# Thetis_RevF2_SCH.net
KiCad netlist of a schematic drawn in EAGLE
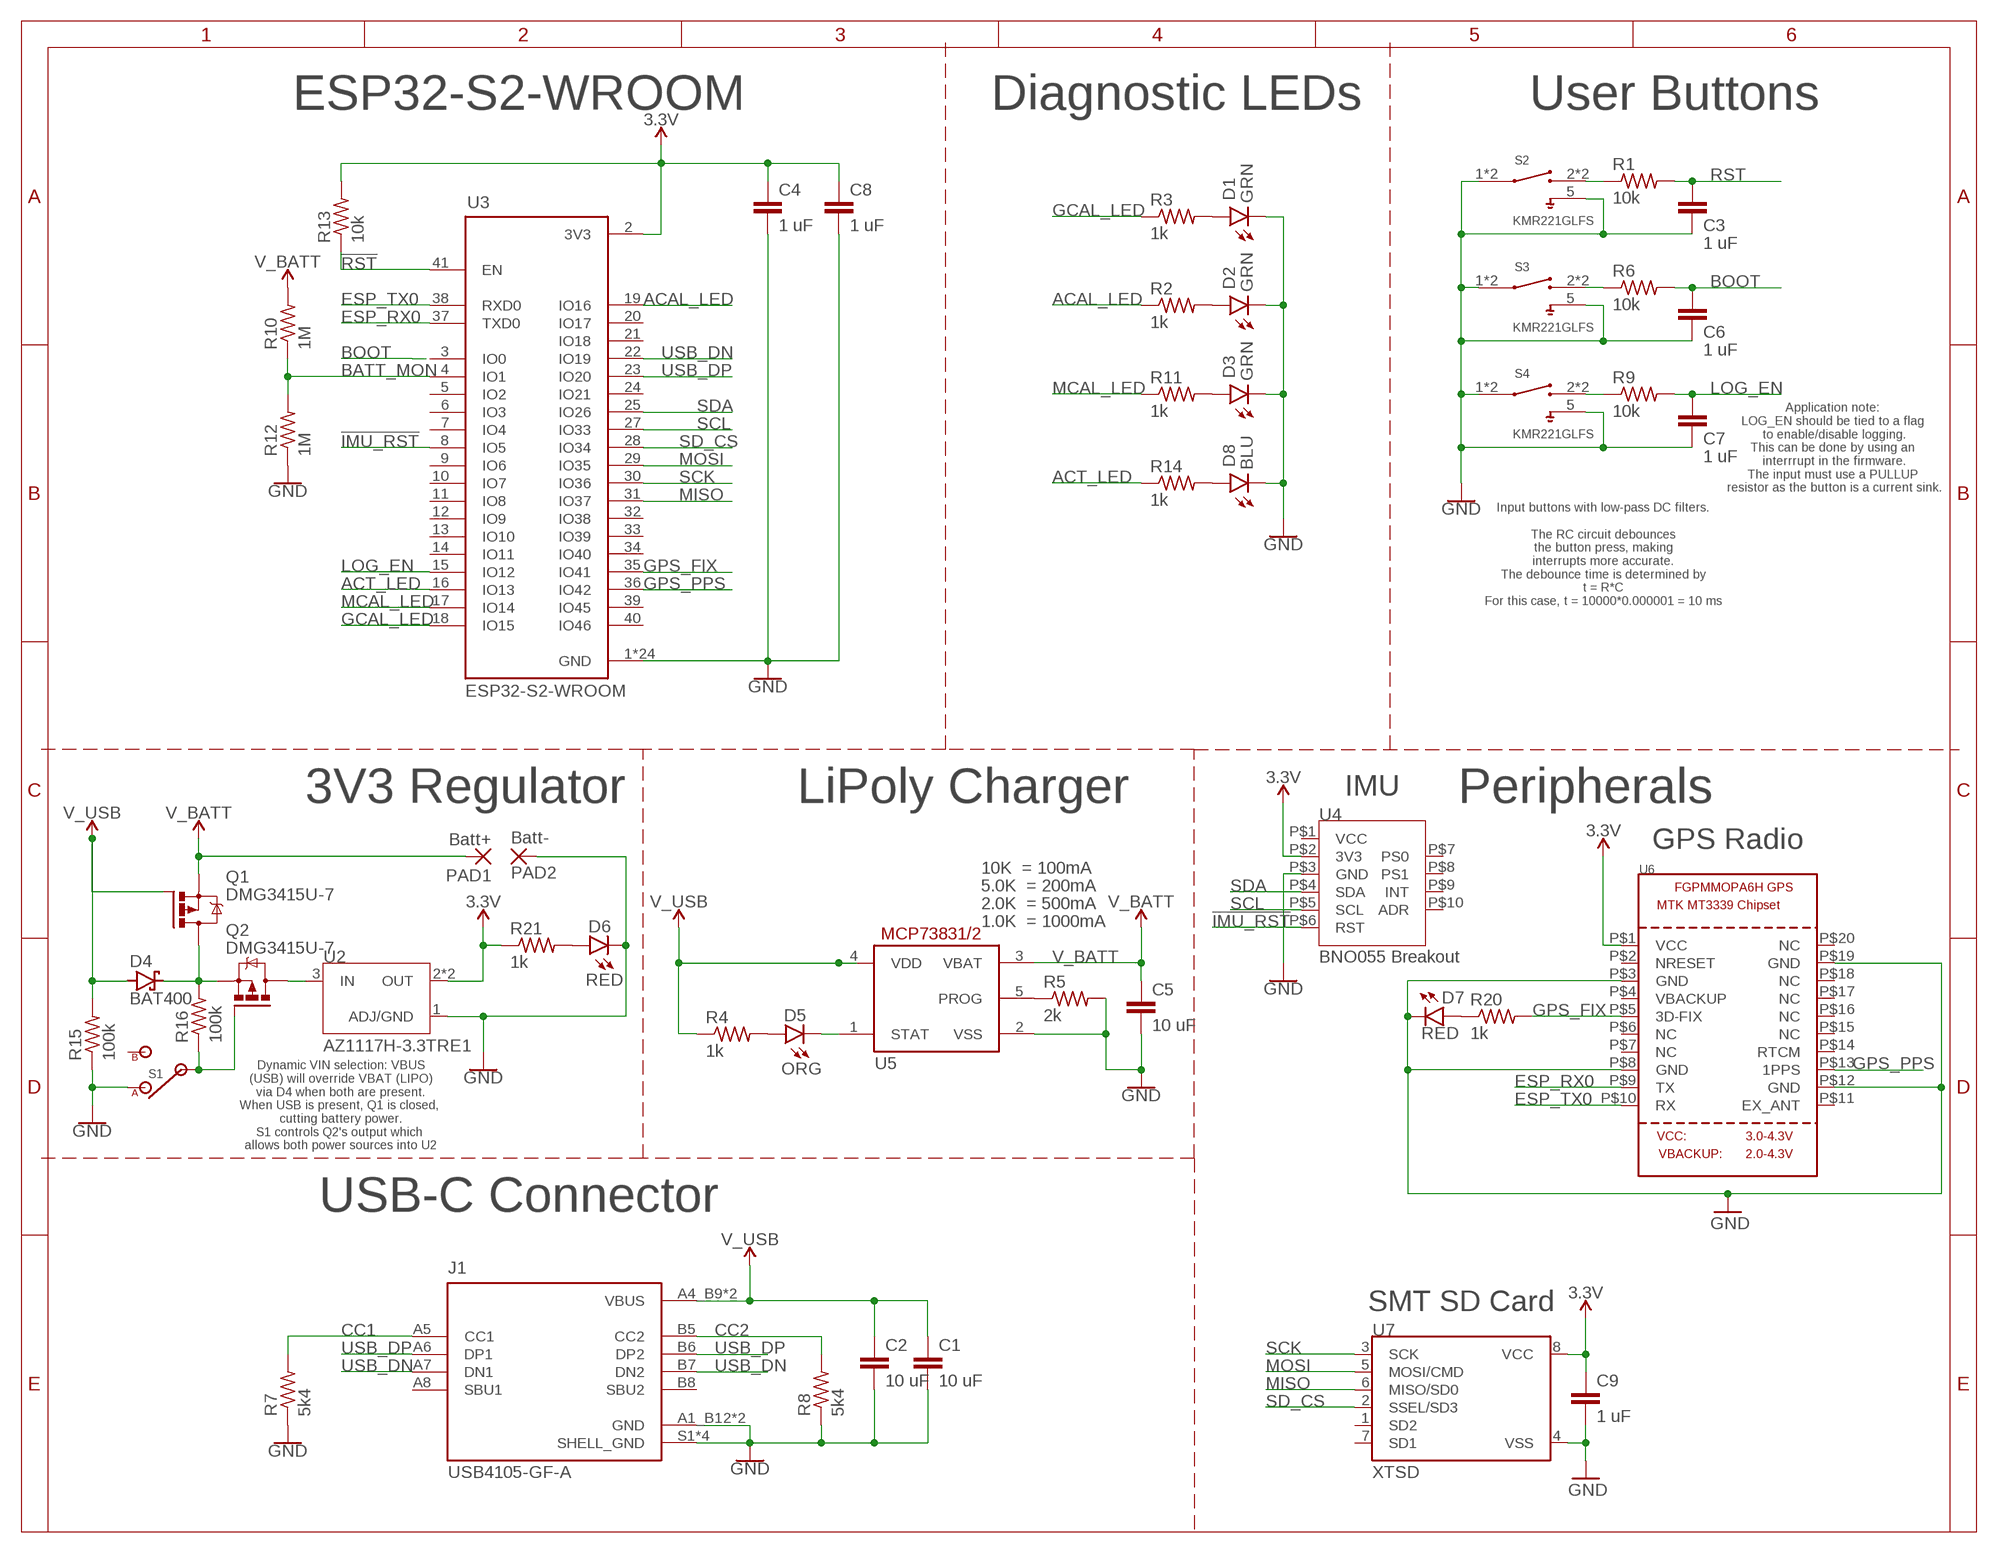
[diagram p0: schematic, sheet 1]

(export (version "E")
  (design (tool "Eeschema 10.0.6"))
  (components
    (comp (ref "C1")
      (value "10 uF")
      (footprint "eagle-import:C0603")
      (libsource (lib "eagle-import") (part "C-EUC0603"))
    )
    (comp (ref "C2")
      (value "10 uF")
      (footprint "eagle-import:C0603")
      (libsource (lib "eagle-import") (part "C-EUC0603"))
    )
    (comp (ref "C3")
      (value "1 uF")
      (footprint "eagle-import:C0603")
      (libsource (lib "eagle-import") (part "C-EUC0603"))
    )
    (comp (ref "C4")
      (value "1 uF")
      (footprint "eagle-import:C0603")
      (libsource (lib "eagle-import") (part "C-EUC0603"))
    )
    (comp (ref "C5")
      (value "10 uF")
      (footprint "eagle-import:C0603")
      (libsource (lib "eagle-import") (part "C-EUC0603"))
    )
    (comp (ref "C6")
      (value "1 uF")
      (footprint "eagle-import:C0603")
      (libsource (lib "eagle-import") (part "C-EUC0603"))
    )
    (comp (ref "C7")
      (value "1 uF")
      (footprint "eagle-import:C0603")
      (libsource (lib "eagle-import") (part "C-EUC0603"))
    )
    (comp (ref "C8")
      (value "1 uF")
      (footprint "eagle-import:C0603")
      (libsource (lib "eagle-import") (part "C-EUC0603"))
    )
    (comp (ref "C9")
      (value "1 uF")
      (footprint "eagle-import:C0603")
      (libsource (lib "eagle-import") (part "C-EUC0603"))
    )
    (comp (ref "D1")
      (value "GRN")
      (footprint "eagle-import:LEDC1608X65N")
      (libsource (lib "eagle-import") (part "CHIP-ROUND-G_0603"))
    )
    (comp (ref "D2")
      (value "GRN")
      (footprint "eagle-import:LEDC1608X65N")
      (libsource (lib "eagle-import") (part "CHIP-ROUND-G_0603"))
    )
    (comp (ref "D3")
      (value "GRN")
      (footprint "eagle-import:LEDC1608X65N")
      (libsource (lib "eagle-import") (part "CHIP-ROUND-G_0603"))
    )
    (comp (ref "D4")
      (value "BAT400")
      (footprint "eagle-import:SOT23")
      (libsource (lib "eagle-import") (part "BAS40"))
    )
    (comp (ref "D5")
      (value "ORG")
      (footprint "eagle-import:LEDC1608X65N")
      (libsource (lib "eagle-import") (part "CHIP-ROUND-G_0603"))
    )
    (comp (ref "D6")
      (value "RED")
      (footprint "eagle-import:LEDC1608X65N")
      (libsource (lib "eagle-import") (part "CHIP-ROUND-G_0603"))
    )
    (comp (ref "D7")
      (value "RED")
      (footprint "eagle-import:LEDC1608X35N")
      (libsource (lib "eagle-import") (part "CHIP-FLAT-Y_0603-0.35MM"))
    )
    (comp (ref "D8")
      (value "BLU")
      (footprint "eagle-import:LEDC1608X65N")
      (libsource (lib "eagle-import") (part "CHIP-ROUND-G_0603"))
    )
    (comp (ref "J1")
      (value "USB4105-GF-A")
      (footprint "eagle-import:GCT_USB4105-GF-A")
      (fields (field (name "MF") "GCT"))
      (libsource (lib "eagle-import") (part "USB4105-GF-A"))
    )
    (comp (ref "PAD1")
      (value "Batt+")
      (footprint "eagle-import:SMD2,54-5,08")
      (libsource (lib "eagle-import") (part "SMD5"))
    )
    (comp (ref "PAD2")
      (value "Batt-")
      (footprint "eagle-import:SMD2,54-5,08")
      (libsource (lib "eagle-import") (part "SMD5"))
    )
    (comp (ref "Q1")
      (value "DMG3415U-7")
      (footprint "eagle-import:SOT23")
      (fields (field (name "MANUFACTURER") "ON Semiconductor") (field (name "MPN") "BSS84"))
      (libsource (lib "eagle-import") (part "PMOSFET_BSS84"))
    )
    (comp (ref "Q2")
      (value "DMG3415U-7")
      (footprint "eagle-import:SOT23")
      (fields (field (name "MANUFACTURER") "ON Semiconductor") (field (name "MPN") "BSS84"))
      (libsource (lib "eagle-import") (part "PMOSFET_BSS84"))
    )
    (comp (ref "R1")
      (value "10k")
      (footprint "eagle-import:R0603")
      (libsource (lib "eagle-import") (part "R-US_R0603"))
    )
    (comp (ref "R2")
      (value "1k")
      (footprint "eagle-import:R0603")
      (libsource (lib "eagle-import") (part "R-US_R0603"))
    )
    (comp (ref "R3")
      (value "1k")
      (footprint "eagle-import:R0603")
      (libsource (lib "eagle-import") (part "R-US_R0603"))
    )
    (comp (ref "R4")
      (value "1k")
      (footprint "eagle-import:R0603")
      (libsource (lib "eagle-import") (part "R-US_R0603"))
    )
    (comp (ref "R5")
      (value "2k")
      (footprint "eagle-import:R0603")
      (libsource (lib "eagle-import") (part "R-US_R0603"))
    )
    (comp (ref "R6")
      (value "10k")
      (footprint "eagle-import:R0603")
      (libsource (lib "eagle-import") (part "R-US_R0603"))
    )
    (comp (ref "R7")
      (value "5k4")
      (footprint "eagle-import:R0603")
      (libsource (lib "eagle-import") (part "R-US_R0603"))
    )
    (comp (ref "R8")
      (value "5k4")
      (footprint "eagle-import:R0603")
      (libsource (lib "eagle-import") (part "R-US_R0603"))
    )
    (comp (ref "R9")
      (value "10k")
      (footprint "eagle-import:R0603")
      (libsource (lib "eagle-import") (part "R-US_R0603"))
    )
    (comp (ref "R10")
      (value "1M")
      (footprint "eagle-import:R0603")
      (libsource (lib "eagle-import") (part "R-US_R0603"))
    )
    (comp (ref "R11")
      (value "1k")
      (footprint "eagle-import:R0603")
      (libsource (lib "eagle-import") (part "R-US_R0603"))
    )
    (comp (ref "R12")
      (value "1M")
      (footprint "eagle-import:R0603")
      (libsource (lib "eagle-import") (part "R-US_R0603"))
    )
    (comp (ref "R13")
      (value "10k")
      (footprint "eagle-import:R0603")
      (libsource (lib "eagle-import") (part "R-US_R0603"))
    )
    (comp (ref "R14")
      (value "1k")
      (footprint "eagle-import:R0603")
      (libsource (lib "eagle-import") (part "R-US_R0603"))
    )
    (comp (ref "R15")
      (value "100k")
      (footprint "eagle-import:R0603")
      (libsource (lib "eagle-import") (part "R-US_R0603"))
    )
    (comp (ref "R16")
      (value "100k")
      (footprint "eagle-import:R0603")
      (libsource (lib "eagle-import") (part "R-US_R0603"))
    )
    (comp (ref "R20")
      (value "1k")
      (footprint "eagle-import:R0603")
      (libsource (lib "eagle-import") (part "R-US_R0603"))
    )
    (comp (ref "R21")
      (value "1k")
      (footprint "eagle-import:R0603")
      (libsource (lib "eagle-import") (part "R-US_R0603"))
    )
    (comp (ref "S1")
      (value "CL-SB-12X")
      (footprint "eagle-import:CL-SB-12A")
      (libsource (lib "eagle-import") (part "CL-SB-12X"))
    )
    (comp (ref "S2")
      (value "KMR221GLFS")
      (footprint "eagle-import:SW_KMR221GLFS")
      (fields (field (name "MANUFACTURER") "CnK"))
      (libsource (lib "eagle-import") (part "KMR221GLFS"))
    )
    (comp (ref "S3")
      (value "KMR221GLFS")
      (footprint "eagle-import:SW_KMR221GLFS")
      (fields (field (name "MANUFACTURER") "CnK"))
      (libsource (lib "eagle-import") (part "KMR221GLFS"))
    )
    (comp (ref "S4")
      (value "KMR221GLFS")
      (footprint "eagle-import:SW_KMR221GLFS")
      (fields (field (name "MANUFACTURER") "CnK"))
      (libsource (lib "eagle-import") (part "KMR221GLFS"))
    )
    (comp (ref "U2")
      (value "AZ1117H-3.3TRE1")
      (footprint "eagle-import:SOT230P700X180-4N")
      (fields (field (name "MF") "Diodes Inc.") (field (name "MP") "AZ1117EH-5.0TRG1"))
      (libsource (lib "eagle-import") (part "AZ1117EH-5.0TRG1"))
    )
    (comp (ref "U3")
      (value "ESP32-S2-WROOM")
      (footprint "eagle-import:XCVR_ESP32-S2-WROOM")
      (fields (field (name "MANUFACTURER") "Espressif Systems"))
      (libsource (lib "eagle-import") (part "ESP32-S2-WROOM"))
    )
    (comp (ref "U4")
      (value "BNO055 Breakout")
      (footprint "eagle-import:ADAFRUIT-BNO055-BREAKOUT-SMD")
      (libsource (lib "eagle-import") (part "ADAFRUIT-BNO055-BREAKOUT-SMD"))
    )
    (comp (ref "U5")
      (value "MCP73831/OT")
      (footprint "eagle-import:SOT23-5L")
      (libsource (lib "eagle-import") (part "MCP73831/OT"))
    )
    (comp (ref "U6")
      (value "GPS_FGPMMOPA6H")
      (footprint "eagle-import:FGPMMOPA6H")
      (libsource (lib "eagle-import") (part "GPS_FGPMMOPA6H"))
    )
    (comp (ref "U7")
      (value "XTSD")
      (footprint "eagle-import:LGA8_8X6")
      (libsource (lib "eagle-import") (part "SMT_SDCARD_8PIN"))
    )
  )
  (nets
    (net (code "1") (name "/ACAL_LED") (class "Default")
      (node (ref "R2") (pin "1") (pinfunction "1_1") (pintype "passive"))
      (node (ref "U3") (pin "19") (pinfunction "IO16_19") (pintype "bidirectional"))
    )
    (net (code "2") (name "/ACT_LED") (class "Default")
      (node (ref "R14") (pin "1") (pinfunction "1_1") (pintype "passive"))
      (node (ref "U3") (pin "16") (pinfunction "IO13_16") (pintype "bidirectional"))
    )
    (net (code "3") (name "/BATT_MON") (class "Default")
      (node (ref "R10") (pin "1") (pinfunction "1_1") (pintype "passive"))
      (node (ref "R12") (pin "2") (pinfunction "2_2") (pintype "passive"))
      (node (ref "U3") (pin "4") (pinfunction "IO1_4") (pintype "bidirectional"))
    )
    (net (code "4") (name "/BOOT") (class "Default")
      (node (ref "C6") (pin "1") (pinfunction "1_1") (pintype "passive"))
      (node (ref "R6") (pin "2") (pinfunction "2_2") (pintype "passive"))
      (node (ref "U3") (pin "3") (pinfunction "IO0_3") (pintype "bidirectional"))
    )
    (net (code "5") (name "/CC1") (class "Default")
      (node (ref "J1") (pin "A5") (pinfunction "CC1_A5") (pintype "bidirectional"))
      (node (ref "R7") (pin "2") (pinfunction "2_2") (pintype "passive"))
    )
    (net (code "6") (name "/CC2") (class "Default")
      (node (ref "J1") (pin "B5") (pinfunction "CC2_B5") (pintype "bidirectional"))
      (node (ref "R8") (pin "2") (pinfunction "2_2") (pintype "passive"))
    )
    (net (code "7") (name "/ESP_RX0") (class "Default")
      (node (ref "U3") (pin "37") (pinfunction "TXD0_37") (pintype "bidirectional"))
      (node (ref "U6") (pin "P$9") (pinfunction "TX_P$9") (pintype "bidirectional"))
    )
    (net (code "8") (name "/ESP_TX0") (class "Default")
      (node (ref "U3") (pin "38") (pinfunction "RXD0_38") (pintype "bidirectional"))
      (node (ref "U6") (pin "P$10") (pinfunction "RX_P$10") (pintype "bidirectional"))
    )
    (net (code "9") (name "/GCAL_LED") (class "Default")
      (node (ref "R3") (pin "1") (pinfunction "1_1") (pintype "passive"))
      (node (ref "U3") (pin "18") (pinfunction "IO15_18") (pintype "bidirectional"))
    )
    (net (code "10") (name "/GPS_FIX") (class "Default")
      (node (ref "R20") (pin "2") (pinfunction "2_2") (pintype "passive"))
      (node (ref "U3") (pin "35") (pinfunction "IO41_35") (pintype "bidirectional"))
      (node (ref "U6") (pin "P$5") (pinfunction "3D-FIX_P$5") (pintype "bidirectional"))
    )
    (net (code "11") (name "/GPS_PPS") (class "Default")
      (node (ref "U3") (pin "36") (pinfunction "IO42_36") (pintype "bidirectional"))
      (node (ref "U6") (pin "P$13") (pinfunction "1PPS_P$13") (pintype "bidirectional"))
    )
    (net (code "12") (name "/LOG_EN") (class "Default")
      (node (ref "C7") (pin "1") (pinfunction "1_1") (pintype "passive"))
      (node (ref "R9") (pin "2") (pinfunction "2_2") (pintype "passive"))
      (node (ref "U3") (pin "15") (pinfunction "IO12_15") (pintype "bidirectional"))
    )
    (net (code "13") (name "/MCAL_LED") (class "Default")
      (node (ref "R11") (pin "1") (pinfunction "1_1") (pintype "passive"))
      (node (ref "U3") (pin "17") (pinfunction "IO14_17") (pintype "bidirectional"))
    )
    (net (code "14") (name "/MISO") (class "Default")
      (node (ref "U3") (pin "31") (pinfunction "IO37_31") (pintype "bidirectional"))
      (node (ref "U7") (pin "6") (pinfunction "MISO/SD0_6") (pintype "bidirectional"))
    )
    (net (code "15") (name "/MOSI") (class "Default")
      (node (ref "U3") (pin "29") (pinfunction "IO35_29") (pintype "bidirectional"))
      (node (ref "U7") (pin "5") (pinfunction "MOSI/CMD_5") (pintype "bidirectional"))
    )
    (net (code "16") (name "/RST") (class "Default")
      (node (ref "C3") (pin "1") (pinfunction "1_1") (pintype "passive"))
      (node (ref "R1") (pin "2") (pinfunction "2_2") (pintype "passive"))
    )
    (net (code "17") (name "/SCK") (class "Default")
      (node (ref "U3") (pin "30") (pinfunction "IO36_30") (pintype "bidirectional"))
      (node (ref "U7") (pin "3") (pinfunction "SCK_3") (pintype "input"))
    )
    (net (code "18") (name "/SCL") (class "Default")
      (node (ref "U3") (pin "27") (pinfunction "IO33_27") (pintype "bidirectional"))
      (node (ref "U4") (pin "P$5") (pinfunction "SCL_P$5") (pintype "bidirectional"))
    )
    (net (code "19") (name "/SDA") (class "Default")
      (node (ref "U3") (pin "25") (pinfunction "IO26_25") (pintype "bidirectional"))
      (node (ref "U4") (pin "P$4") (pinfunction "SDA_P$4") (pintype "bidirectional"))
    )
    (net (code "20") (name "/SD_CS") (class "Default")
      (node (ref "U3") (pin "28") (pinfunction "IO34_28") (pintype "bidirectional"))
      (node (ref "U7") (pin "2") (pinfunction "SSEL/SD3_2") (pintype "bidirectional"))
    )
    (net (code "21") (name "/USB_DN") (class "Default")
      (node (ref "J1") (pin "A7") (pinfunction "DN1_A7") (pintype "bidirectional"))
      (node (ref "J1") (pin "B7") (pinfunction "DN2_B7") (pintype "bidirectional"))
      (node (ref "U3") (pin "22") (pinfunction "IO19_22") (pintype "bidirectional"))
    )
    (net (code "22") (name "/USB_DP") (class "Default")
      (node (ref "J1") (pin "A6") (pinfunction "DP1_A6") (pintype "bidirectional"))
      (node (ref "J1") (pin "B6") (pinfunction "DP2_B6") (pintype "bidirectional"))
      (node (ref "U3") (pin "23") (pinfunction "IO20_23") (pintype "bidirectional"))
    )
    (net (code "23") (name "/VCC") (class "Default")
      (node (ref "U4") (pin "P$1") (pinfunction "VCC_P$1") (pintype "power_in"))
    )
    (net (code "24") (name "/~{IMU_RST}") (class "Default")
      (node (ref "U3") (pin "8") (pinfunction "IO5_8") (pintype "bidirectional"))
      (node (ref "U4") (pin "P$6") (pinfunction "RST_P$6") (pintype "input"))
    )
    (net (code "25") (name "/~{RST}") (class "Default")
      (node (ref "R13") (pin "1") (pinfunction "1_1") (pintype "passive"))
      (node (ref "U3") (pin "41") (pinfunction "EN_41") (pintype "input"))
    )
    (net (code "26") (name "3.3V") (class "Default")
      (node (ref "C4") (pin "1") (pinfunction "1_1") (pintype "passive"))
      (node (ref "C8") (pin "1") (pinfunction "1_1") (pintype "passive"))
      (node (ref "C9") (pin "1") (pinfunction "1_1") (pintype "passive"))
      (node (ref "R13") (pin "2") (pinfunction "2_2") (pintype "passive"))
      (node (ref "R21") (pin "1") (pinfunction "1_1") (pintype "passive"))
      (node (ref "U2") (pin "2") (pinfunction "OUT_2") (pintype "output"))
      (node (ref "U2") (pin "4") (pinfunction "OUT_4") (pintype "output"))
      (node (ref "U3") (pin "2") (pinfunction "3V3_2") (pintype "power_in"))
      (node (ref "U4") (pin "P$2") (pinfunction "3V3_P$2") (pintype "power_in"))
      (node (ref "U6") (pin "P$1") (pinfunction "VCC_P$1") (pintype "bidirectional"))
      (node (ref "U7") (pin "8") (pinfunction "VCC_8") (pintype "power_in"))
    )
    (net (code "27") (name "GND") (class "Default")
      (node (ref "C1") (pin "2") (pinfunction "2_2") (pintype "passive"))
      (node (ref "C2") (pin "2") (pinfunction "2_2") (pintype "passive"))
      (node (ref "C3") (pin "2") (pinfunction "2_2") (pintype "passive"))
      (node (ref "C4") (pin "2") (pinfunction "2_2") (pintype "passive"))
      (node (ref "C5") (pin "2") (pinfunction "2_2") (pintype "passive"))
      (node (ref "C6") (pin "2") (pinfunction "2_2") (pintype "passive"))
      (node (ref "C7") (pin "2") (pinfunction "2_2") (pintype "passive"))
      (node (ref "C8") (pin "2") (pinfunction "2_2") (pintype "passive"))
      (node (ref "C9") (pin "2") (pinfunction "2_2") (pintype "passive"))
      (node (ref "D1") (pin "C") (pinfunction "C_C") (pintype "passive"))
      (node (ref "D2") (pin "C") (pinfunction "C_C") (pintype "passive"))
      (node (ref "D3") (pin "C") (pinfunction "C_C") (pintype "passive"))
      (node (ref "D6") (pin "C") (pinfunction "C_C") (pintype "passive"))
      (node (ref "D7") (pin "C") (pinfunction "C_C") (pintype "passive"))
      (node (ref "D8") (pin "C") (pinfunction "C_C") (pintype "passive"))
      (node (ref "J1") (pin "A1_B12") (pinfunction "GND_A1_B12") (pintype "power_in"))
      (node (ref "J1") (pin "B1_A12") (pinfunction "GND_B1_A12") (pintype "power_in"))
      (node (ref "J1") (pin "S1") (pinfunction "SHELL_GND_S1") (pintype "power_in"))
      (node (ref "J1") (pin "S2") (pinfunction "SHELL_GND_S2") (pintype "power_in"))
      (node (ref "J1") (pin "S3") (pinfunction "SHELL_GND_S3") (pintype "power_in"))
      (node (ref "J1") (pin "S4") (pinfunction "SHELL_GND_S4") (pintype "power_in"))
      (node (ref "PAD2") (pin "1") (pinfunction "P_1") (pintype "passive"))
      (node (ref "R12") (pin "1") (pinfunction "1_1") (pintype "passive"))
      (node (ref "R15") (pin "1") (pinfunction "1_1") (pintype "passive"))
      (node (ref "R5") (pin "2") (pinfunction "2_2") (pintype "passive"))
      (node (ref "R7") (pin "1") (pinfunction "1_1") (pintype "passive"))
      (node (ref "R8") (pin "1") (pinfunction "1_1") (pintype "passive"))
      (node (ref "S1") (pin "1") (pinfunction "1_1") (pintype "bidirectional"))
      (node (ref "S2") (pin "1") (pinfunction "1_1") (pintype "passive"))
      (node (ref "S2") (pin "4") (pinfunction "1_4") (pintype "passive"))
      (node (ref "S2") (pin "5") (pinfunction "5_5") (pintype "passive"))
      (node (ref "S3") (pin "1") (pinfunction "1_1") (pintype "passive"))
      (node (ref "S3") (pin "4") (pinfunction "1_4") (pintype "passive"))
      (node (ref "S3") (pin "5") (pinfunction "5_5") (pintype "passive"))
      (node (ref "S4") (pin "1") (pinfunction "1_1") (pintype "passive"))
      (node (ref "S4") (pin "4") (pinfunction "1_4") (pintype "passive"))
      (node (ref "S4") (pin "5") (pinfunction "5_5") (pintype "passive"))
      (node (ref "U2") (pin "1") (pinfunction "ADJ/GND_1") (pintype "power_in"))
      (node (ref "U3") (pin "1") (pinfunction "GND_1") (pintype "power_in"))
      (node (ref "U3") (pin "26") (pinfunction "GND_26") (pintype "power_in"))
      (node (ref "U3") (pin "42") (pinfunction "GND_42") (pintype "power_in"))
      (node (ref "U3") (pin "43.1") (pinfunction "GND_43.1") (pintype "power_in"))
      (node (ref "U3") (pin "43.10") (pinfunction "GND_43.10") (pintype "power_in"))
      (node (ref "U3") (pin "43.11") (pinfunction "GND_43.11") (pintype "power_in"))
      (node (ref "U3") (pin "43.12") (pinfunction "GND_43.12") (pintype "power_in"))
      (node (ref "U3") (pin "43.13") (pinfunction "GND_43.13") (pintype "power_in"))
      (node (ref "U3") (pin "43.14") (pinfunction "GND_43.14") (pintype "power_in"))
      (node (ref "U3") (pin "43.15") (pinfunction "GND_43.15") (pintype "power_in"))
      (node (ref "U3") (pin "43.16") (pinfunction "GND_43.16") (pintype "power_in"))
      (node (ref "U3") (pin "43.17") (pinfunction "GND_43.17") (pintype "power_in"))
      (node (ref "U3") (pin "43.18") (pinfunction "GND_43.18") (pintype "power_in"))
      (node (ref "U3") (pin "43.19") (pinfunction "GND_43.19") (pintype "power_in"))
      (node (ref "U3") (pin "43.2") (pinfunction "GND_43.2") (pintype "power_in"))
      (node (ref "U3") (pin "43.20") (pinfunction "GND_43.20") (pintype "power_in"))
      (node (ref "U3") (pin "43.21") (pinfunction "GND_43.21") (pintype "power_in"))
      (node (ref "U3") (pin "43.3") (pinfunction "GND_43.3") (pintype "power_in"))
      (node (ref "U3") (pin "43.4") (pinfunction "GND_43.4") (pintype "power_in"))
      (node (ref "U3") (pin "43.5") (pinfunction "GND_43.5") (pintype "power_in"))
      (node (ref "U3") (pin "43.6") (pinfunction "GND_43.6") (pintype "power_in"))
      (node (ref "U3") (pin "43.7") (pinfunction "GND_43.7") (pintype "power_in"))
      (node (ref "U3") (pin "43.8") (pinfunction "GND_43.8") (pintype "power_in"))
      (node (ref "U3") (pin "43.9") (pinfunction "GND_43.9") (pintype "power_in"))
      (node (ref "U4") (pin "P$3") (pinfunction "GND_P$3") (pintype "power_in"))
      (node (ref "U5") (pin "2") (pinfunction "VSS_2") (pintype "power_in"))
      (node (ref "U6") (pin "P$12") (pinfunction "GND_P$12") (pintype "bidirectional"))
      (node (ref "U6") (pin "P$19") (pinfunction "GND_P$19") (pintype "bidirectional"))
      (node (ref "U6") (pin "P$3") (pinfunction "GND_P$3") (pintype "bidirectional"))
      (node (ref "U6") (pin "P$8") (pinfunction "GND_P$8") (pintype "bidirectional"))
      (node (ref "U7") (pin "4") (pinfunction "VSS_4") (pintype "power_in"))
    )
    (net (code "28") (name "Net-(D1-PadA)") (class "Default")
      (node (ref "D1") (pin "A") (pinfunction "A_A") (pintype "passive"))
      (node (ref "R3") (pin "2") (pinfunction "2_2") (pintype "passive"))
    )
    (net (code "29") (name "Net-(D2-PadA)") (class "Default")
      (node (ref "D2") (pin "A") (pinfunction "A_A") (pintype "passive"))
      (node (ref "R2") (pin "2") (pinfunction "2_2") (pintype "passive"))
    )
    (net (code "30") (name "Net-(D3-PadA)") (class "Default")
      (node (ref "D3") (pin "A") (pinfunction "A_A") (pintype "passive"))
      (node (ref "R11") (pin "2") (pinfunction "2_2") (pintype "passive"))
    )
    (net (code "31") (name "Net-(D4-C)") (class "Default")
      (node (ref "D4") (pin "3") (pinfunction "C_3") (pintype "passive"))
      (node (ref "Q1") (pin "3") (pinfunction "D_3") (pintype "passive"))
      (node (ref "Q2") (pin "2") (pinfunction "S_2") (pintype "passive"))
      (node (ref "R16") (pin "2") (pinfunction "2_2") (pintype "passive"))
    )
    (net (code "32") (name "Net-(D5-PadA)") (class "Default")
      (node (ref "D5") (pin "A") (pinfunction "A_A") (pintype "passive"))
      (node (ref "R4") (pin "2") (pinfunction "2_2") (pintype "passive"))
    )
    (net (code "33") (name "Net-(D6-PadA)") (class "Default")
      (node (ref "D6") (pin "A") (pinfunction "A_A") (pintype "passive"))
      (node (ref "R21") (pin "2") (pinfunction "2_2") (pintype "passive"))
    )
    (net (code "34") (name "Net-(D7-PadA)") (class "Default")
      (node (ref "D7") (pin "A") (pinfunction "A_A") (pintype "passive"))
      (node (ref "R20") (pin "1") (pinfunction "1_1") (pintype "passive"))
    )
    (net (code "35") (name "Net-(D8-PadA)") (class "Default")
      (node (ref "D8") (pin "A") (pinfunction "A_A") (pintype "passive"))
      (node (ref "R14") (pin "2") (pinfunction "2_2") (pintype "passive"))
    )
    (net (code "36") (name "Net-(Q2-D)") (class "Default")
      (node (ref "Q2") (pin "3") (pinfunction "D_3") (pintype "passive"))
      (node (ref "U2") (pin "3") (pinfunction "IN_3") (pintype "input"))
    )
    (net (code "37") (name "Net-(Q2-G)") (class "Default")
      (node (ref "Q2") (pin "1") (pinfunction "G_1") (pintype "passive"))
      (node (ref "R16") (pin "1") (pinfunction "1_1") (pintype "passive"))
      (node (ref "S1") (pin "2") (pinfunction "2_2") (pintype "bidirectional"))
    )
    (net (code "38") (name "Net-(R1-Pad1)") (class "Default")
      (node (ref "R1") (pin "1") (pinfunction "1_1") (pintype "passive"))
      (node (ref "S2") (pin "2") (pinfunction "3_2") (pintype "passive"))
      (node (ref "S2") (pin "3") (pinfunction "3_3") (pintype "passive"))
    )
    (net (code "39") (name "Net-(R6-Pad1)") (class "Default")
      (node (ref "R6") (pin "1") (pinfunction "1_1") (pintype "passive"))
      (node (ref "S3") (pin "2") (pinfunction "3_2") (pintype "passive"))
      (node (ref "S3") (pin "3") (pinfunction "3_3") (pintype "passive"))
    )
    (net (code "40") (name "Net-(R9-Pad1)") (class "Default")
      (node (ref "R9") (pin "1") (pinfunction "1_1") (pintype "passive"))
      (node (ref "S4") (pin "2") (pinfunction "3_2") (pintype "passive"))
      (node (ref "S4") (pin "3") (pinfunction "3_3") (pintype "passive"))
    )
    (net (code "41") (name "Net-(U5-PROG)") (class "Default")
      (node (ref "R5") (pin "1") (pinfunction "1_1") (pintype "passive"))
      (node (ref "U5") (pin "5") (pinfunction "PROG_5") (pintype "input"))
    )
    (net (code "42") (name "Net-(U5-STAT)") (class "Default")
      (node (ref "D5") (pin "C") (pinfunction "C_C") (pintype "passive"))
      (node (ref "U5") (pin "1") (pinfunction "STAT_1") (pintype "output"))
    )
    (net (code "43") (name "V_BATT") (class "Default")
      (node (ref "C5") (pin "1") (pinfunction "1_1") (pintype "passive"))
      (node (ref "PAD1") (pin "1") (pinfunction "P_1") (pintype "passive"))
      (node (ref "Q1") (pin "2") (pinfunction "S_2") (pintype "passive"))
      (node (ref "R10") (pin "2") (pinfunction "2_2") (pintype "passive"))
      (node (ref "U5") (pin "3") (pinfunction "VBAT_3") (pintype "bidirectional"))
    )
    (net (code "44") (name "V_USB") (class "Default")
      (node (ref "C1") (pin "1") (pinfunction "1_1") (pintype "passive"))
      (node (ref "C2") (pin "1") (pinfunction "1_1") (pintype "passive"))
      (node (ref "D4") (pin "1") (pinfunction "A_1") (pintype "passive"))
      (node (ref "J1") (pin "A4_B9") (pinfunction "VBUS_A4_B9") (pintype "power_in"))
      (node (ref "J1") (pin "B4_A9") (pinfunction "VBUS_B4_A9") (pintype "power_in"))
      (node (ref "Q1") (pin "1") (pinfunction "G_1") (pintype "passive"))
      (node (ref "R15") (pin "2") (pinfunction "2_2") (pintype "passive"))
      (node (ref "R4") (pin "1") (pinfunction "1_1") (pintype "passive"))
      (node (ref "U5") (pin "4") (pinfunction "VDD_4") (pintype "power_in"))
    )
    (net (code "45") (name "unconnected-(J1-SBU1-PadA8)") (class "Default")
      (node (ref "J1") (pin "A8") (pinfunction "SBU1_A8") (pintype "bidirectional"))
    )
    (net (code "46") (name "unconnected-(J1-SBU2-PadB8)") (class "Default")
      (node (ref "J1") (pin "B8") (pinfunction "SBU2_B8") (pintype "bidirectional"))
    )
    (net (code "47") (name "unconnected-(S1-Pad3)") (class "Default")
      (node (ref "S1") (pin "3") (pinfunction "3_3") (pintype "bidirectional"))
    )
    (net (code "48") (name "unconnected-(U3-IO2-Pad5)") (class "Default")
      (node (ref "U3") (pin "5") (pinfunction "IO2_5") (pintype "bidirectional"))
    )
    (net (code "49") (name "unconnected-(U3-IO3-Pad6)") (class "Default")
      (node (ref "U3") (pin "6") (pinfunction "IO3_6") (pintype "bidirectional"))
    )
    (net (code "50") (name "unconnected-(U3-IO4-Pad7)") (class "Default")
      (node (ref "U3") (pin "7") (pinfunction "IO4_7") (pintype "bidirectional"))
    )
    (net (code "51") (name "unconnected-(U3-IO6-Pad9)") (class "Default")
      (node (ref "U3") (pin "9") (pinfunction "IO6_9") (pintype "bidirectional"))
    )
    (net (code "52") (name "unconnected-(U3-IO7-Pad10)") (class "Default")
      (node (ref "U3") (pin "10") (pinfunction "IO7_10") (pintype "bidirectional"))
    )
    (net (code "53") (name "unconnected-(U3-IO8-Pad11)") (class "Default")
      (node (ref "U3") (pin "11") (pinfunction "IO8_11") (pintype "bidirectional"))
    )
    (net (code "54") (name "unconnected-(U3-IO9-Pad12)") (class "Default")
      (node (ref "U3") (pin "12") (pinfunction "IO9_12") (pintype "bidirectional"))
    )
    (net (code "55") (name "unconnected-(U3-IO10-Pad13)") (class "Default")
      (node (ref "U3") (pin "13") (pinfunction "IO10_13") (pintype "bidirectional"))
    )
    (net (code "56") (name "unconnected-(U3-IO11-Pad14)") (class "Default")
      (node (ref "U3") (pin "14") (pinfunction "IO11_14") (pintype "bidirectional"))
    )
    (net (code "57") (name "unconnected-(U3-IO17-Pad20)") (class "Default")
      (node (ref "U3") (pin "20") (pinfunction "IO17_20") (pintype "bidirectional"))
    )
    (net (code "58") (name "unconnected-(U3-IO18-Pad21)") (class "Default")
      (node (ref "U3") (pin "21") (pinfunction "IO18_21") (pintype "bidirectional"))
    )
    (net (code "59") (name "unconnected-(U3-IO21-Pad24)") (class "Default")
      (node (ref "U3") (pin "24") (pinfunction "IO21_24") (pintype "bidirectional"))
    )
    (net (code "60") (name "unconnected-(U3-IO38-Pad32)") (class "Default")
      (node (ref "U3") (pin "32") (pinfunction "IO38_32") (pintype "bidirectional"))
    )
    (net (code "61") (name "unconnected-(U3-IO39-Pad33)") (class "Default")
      (node (ref "U3") (pin "33") (pinfunction "IO39_33") (pintype "bidirectional"))
    )
    (net (code "62") (name "unconnected-(U3-IO40-Pad34)") (class "Default")
      (node (ref "U3") (pin "34") (pinfunction "IO40_34") (pintype "bidirectional"))
    )
    (net (code "63") (name "unconnected-(U3-IO45-Pad39)") (class "Default")
      (node (ref "U3") (pin "39") (pinfunction "IO45_39") (pintype "bidirectional"))
    )
    (net (code "64") (name "unconnected-(U3-IO46-Pad40)") (class "Default")
      (node (ref "U3") (pin "40") (pinfunction "IO46_40") (pintype "bidirectional"))
    )
    (net (code "65") (name "unconnected-(U4-ADR-PadP$10)") (class "Default")
      (node (ref "U4") (pin "P$10") (pinfunction "ADR_P$10") (pintype "bidirectional"))
    )
    (net (code "66") (name "unconnected-(U4-INT-PadP$9)") (class "Default")
      (node (ref "U4") (pin "P$9") (pinfunction "INT_P$9") (pintype "bidirectional"))
    )
    (net (code "67") (name "unconnected-(U4-PS0-PadP$7)") (class "Default")
      (node (ref "U4") (pin "P$7") (pinfunction "PS0_P$7") (pintype "bidirectional"))
    )
    (net (code "68") (name "unconnected-(U4-PS1-PadP$8)") (class "Default")
      (node (ref "U4") (pin "P$8") (pinfunction "PS1_P$8") (pintype "bidirectional"))
    )
    (net (code "69") (name "unconnected-(U6-EX_ANT-PadP$11)") (class "Default")
      (node (ref "U6") (pin "P$11") (pinfunction "EX_ANT_P$11") (pintype "bidirectional"))
    )
    (net (code "70") (name "unconnected-(U6-NC-PadP$6)") (class "Default")
      (node (ref "U6") (pin "P$6") (pinfunction "NC_P$6") (pintype "bidirectional"))
    )
    (net (code "71") (name "unconnected-(U6-NC-PadP$7)") (class "Default")
      (node (ref "U6") (pin "P$7") (pinfunction "NC_P$7") (pintype "bidirectional"))
    )
    (net (code "72") (name "unconnected-(U6-NC-PadP$15)") (class "Default")
      (node (ref "U6") (pin "P$15") (pinfunction "NC_P$15") (pintype "bidirectional"))
    )
    (net (code "73") (name "unconnected-(U6-NC-PadP$16)") (class "Default")
      (node (ref "U6") (pin "P$16") (pinfunction "NC_P$16") (pintype "bidirectional"))
    )
    (net (code "74") (name "unconnected-(U6-NC-PadP$17)") (class "Default")
      (node (ref "U6") (pin "P$17") (pinfunction "NC_P$17") (pintype "bidirectional"))
    )
    (net (code "75") (name "unconnected-(U6-NC-PadP$18)") (class "Default")
      (node (ref "U6") (pin "P$18") (pinfunction "NC_P$18") (pintype "bidirectional"))
    )
    (net (code "76") (name "unconnected-(U6-NC-PadP$20)") (class "Default")
      (node (ref "U6") (pin "P$20") (pinfunction "NC_P$20") (pintype "bidirectional"))
    )
    (net (code "77") (name "unconnected-(U6-NRESET-PadP$2)") (class "Default")
      (node (ref "U6") (pin "P$2") (pinfunction "NRESET_P$2") (pintype "bidirectional"))
    )
    (net (code "78") (name "unconnected-(U6-RTCM-PadP$14)") (class "Default")
      (node (ref "U6") (pin "P$14") (pinfunction "RTCM_P$14") (pintype "bidirectional"))
    )
    (net (code "79") (name "unconnected-(U6-VBACKUP-PadP$4)") (class "Default")
      (node (ref "U6") (pin "P$4") (pinfunction "VBACKUP_P$4") (pintype "bidirectional"))
    )
    (net (code "80") (name "unconnected-(U7-SD1-Pad7)") (class "Default")
      (node (ref "U7") (pin "7") (pinfunction "SD1_7") (pintype "bidirectional"))
    )
    (net (code "81") (name "unconnected-(U7-SD2-Pad1)") (class "Default")
      (node (ref "U7") (pin "1") (pinfunction "SD2_1") (pintype "bidirectional"))
    )
  )
)
